# Peltie.net
KiCad netlist of a schematic drawn in Altium Designer
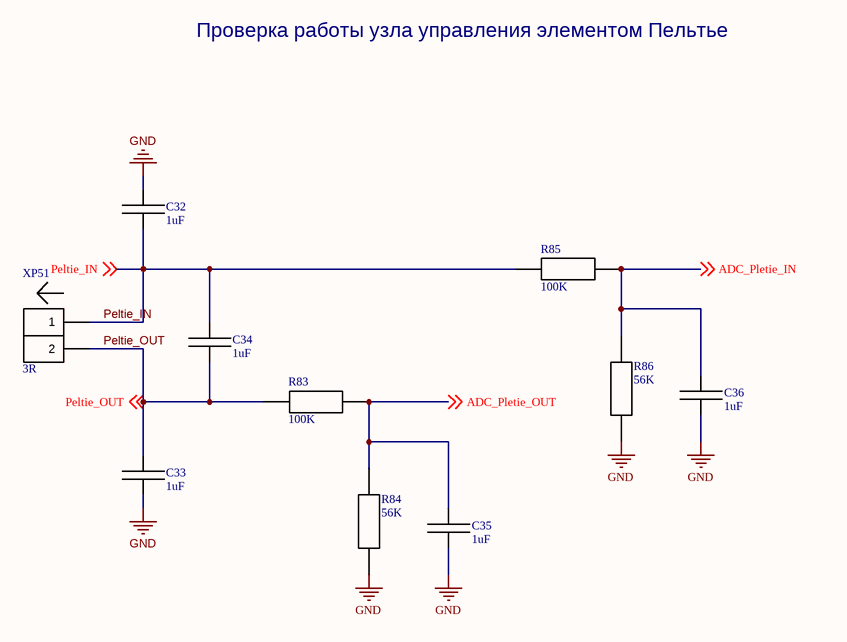
[diagram p0: Peltie.SchDoc]

(export (version "E")
  (design (tool "Eeschema 10.0.6"))
  (components
    (comp (ref "C32")
      (value "1uF")
      (footprint "0603C")
      (description "C0603-1uF 10% 50V")
      (fields
        (field (name "PART NUMBER") "SMD CAP CER 1uF ±10% 50V X7R 0603")
        (field (name "ADDED_BY") "grebelny_av@teslatec.ru")
      )
      (libsource (lib "Test_Stand_Pergam") (part "C0603-1uF 10% 50V"))
    )
    (comp (ref "C33")
      (value "1uF")
      (footprint "0603C")
      (description "C0603-1uF 10% 50V")
      (fields
        (field (name "PART NUMBER") "SMD CAP CER 1uF ±10% 50V X7R 0603")
        (field (name "ADDED_BY") "grebelny_av@teslatec.ru")
      )
      (libsource (lib "Test_Stand_Pergam") (part "C0603-1uF 10% 50V"))
    )
    (comp (ref "C34")
      (value "1uF")
      (footprint "0603C")
      (description "C0603-1uF 10% 50V")
      (fields
        (field (name "PART NUMBER") "SMD CAP CER 1uF ±10% 50V X7R 0603")
        (field (name "ADDED_BY") "grebelny_av@teslatec.ru")
      )
      (libsource (lib "Test_Stand_Pergam") (part "C0603-1uF 10% 50V"))
    )
    (comp (ref "C35")
      (value "1uF")
      (footprint "0603C")
      (description "C0603-1uF 10% 50V")
      (fields
        (field (name "PART NUMBER") "SMD CAP CER 1uF ±10% 50V X7R 0603")
        (field (name "ADDED_BY") "grebelny_av@teslatec.ru")
      )
      (libsource (lib "Test_Stand_Pergam") (part "C0603-1uF 10% 50V"))
    )
    (comp (ref "C36")
      (value "1uF")
      (footprint "0603C")
      (description "C0603-1uF 10% 50V")
      (fields
        (field (name "PART NUMBER") "SMD CAP CER 1uF ±10% 50V X7R 0603")
        (field (name "ADDED_BY") "grebelny_av@teslatec.ru")
      )
      (libsource (lib "Test_Stand_Pergam") (part "C0603-1uF 10% 50V"))
    )
    (comp (ref "R83")
      (value "100K")
      (footprint "R0402")
      (description "Resistor SMD 100K 1% 0402")
      (fields
        (field (name "PART NUMBER") "SMD RES 100 KOHM 1% ±100ppm/°C 0402")
        (field (name "ADDED_BY") "Rutel@teslatec.ru")
      )
      (libsource (lib "Test_Stand_Pergam") (part "R0402-100K"))
    )
    (comp (ref "R84")
      (value "56K")
      (footprint "R0402")
      (description "Resistor SMD 56K 1% 0402")
      (fields
        (field (name "PART NUMBER") "SMD RES 56K KOHM 1% ±100ppm/°C 0402")
        (field (name "ADDED_BY") "ridel_av@teslatec.ru")
      )
      (libsource (lib "Test_Stand_Pergam") (part "R0402-56K"))
    )
    (comp (ref "R85")
      (value "100K")
      (footprint "R0402")
      (description "Resistor SMD 100K 1% 0402")
      (fields
        (field (name "PART NUMBER") "SMD RES 100 KOHM 1% ±100ppm/°C 0402")
        (field (name "ADDED_BY") "Rutel@teslatec.ru")
      )
      (libsource (lib "Test_Stand_Pergam") (part "R0402-100K"))
    )
    (comp (ref "R86")
      (value "56K")
      (footprint "R0402")
      (description "Resistor SMD 56K 1% 0402")
      (fields
        (field (name "PART NUMBER") "SMD RES 56K KOHM 1% ±100ppm/°C 0402")
        (field (name "ADDED_BY") "ridel_av@teslatec.ru")
      )
      (libsource (lib "Test_Stand_Pergam") (part "R0402-56K"))
    )
    (comp (ref "XP51")
      (value "3R")
      (footprint "PLS-2")
      (description "SQP10AJB-3R")
      (fields (field (name "PART NUMBER") "PLS-2") (field (name "ADDED_BY") "irdolgopolowa@yandex.ru"))
      (libsource (lib "Test_Stand_Pergam") (part "PLS-2_peltie"))
    )
  )
  (nets
    (net (code "1") (name "ADC_Pletie_IN") (class "Default")
      (node (ref "C36") (pin "2") (pinfunction "2_2") (pintype "passive"))
      (node (ref "R85") (pin "1") (pinfunction "1_1") (pintype "passive"))
      (node (ref "R86") (pin "1") (pinfunction "1_1") (pintype "passive"))
    )
    (net (code "2") (name "ADC_Pletie_OUT") (class "Default")
      (node (ref "C35") (pin "2") (pinfunction "2_2") (pintype "passive"))
      (node (ref "R83") (pin "1") (pinfunction "1_1") (pintype "passive"))
      (node (ref "R84") (pin "1") (pinfunction "1_1") (pintype "passive"))
    )
    (net (code "3") (name "GND") (class "Default")
      (node (ref "C32") (pin "2") (pinfunction "2_2") (pintype "passive"))
      (node (ref "C33") (pin "2") (pinfunction "2_2") (pintype "passive"))
      (node (ref "C35") (pin "1") (pinfunction "1_1") (pintype "passive"))
      (node (ref "C36") (pin "1") (pinfunction "1_1") (pintype "passive"))
      (node (ref "R84") (pin "2") (pinfunction "2_2") (pintype "passive"))
      (node (ref "R86") (pin "2") (pinfunction "2_2") (pintype "passive"))
    )
    (net (code "4") (name "Peltie_IN") (class "Default")
      (node (ref "C32") (pin "1") (pinfunction "1_1") (pintype "passive"))
      (node (ref "C34") (pin "2") (pinfunction "2_2") (pintype "passive"))
      (node (ref "R85") (pin "2") (pinfunction "2_2") (pintype "passive"))
      (node (ref "XP51") (pin "1") (pinfunction "1_1") (pintype "passive"))
    )
    (net (code "5") (name "Peltie_OUT") (class "Default")
      (node (ref "C33") (pin "1") (pinfunction "1_1") (pintype "passive"))
      (node (ref "C34") (pin "1") (pinfunction "1_1") (pintype "passive"))
      (node (ref "R83") (pin "2") (pinfunction "2_2") (pintype "passive"))
      (node (ref "XP51") (pin "2") (pinfunction "2_2") (pintype "passive"))
    )
  )
)
